# 05_SPI.net
KiCad netlist of a schematic drawn in Altium Designer
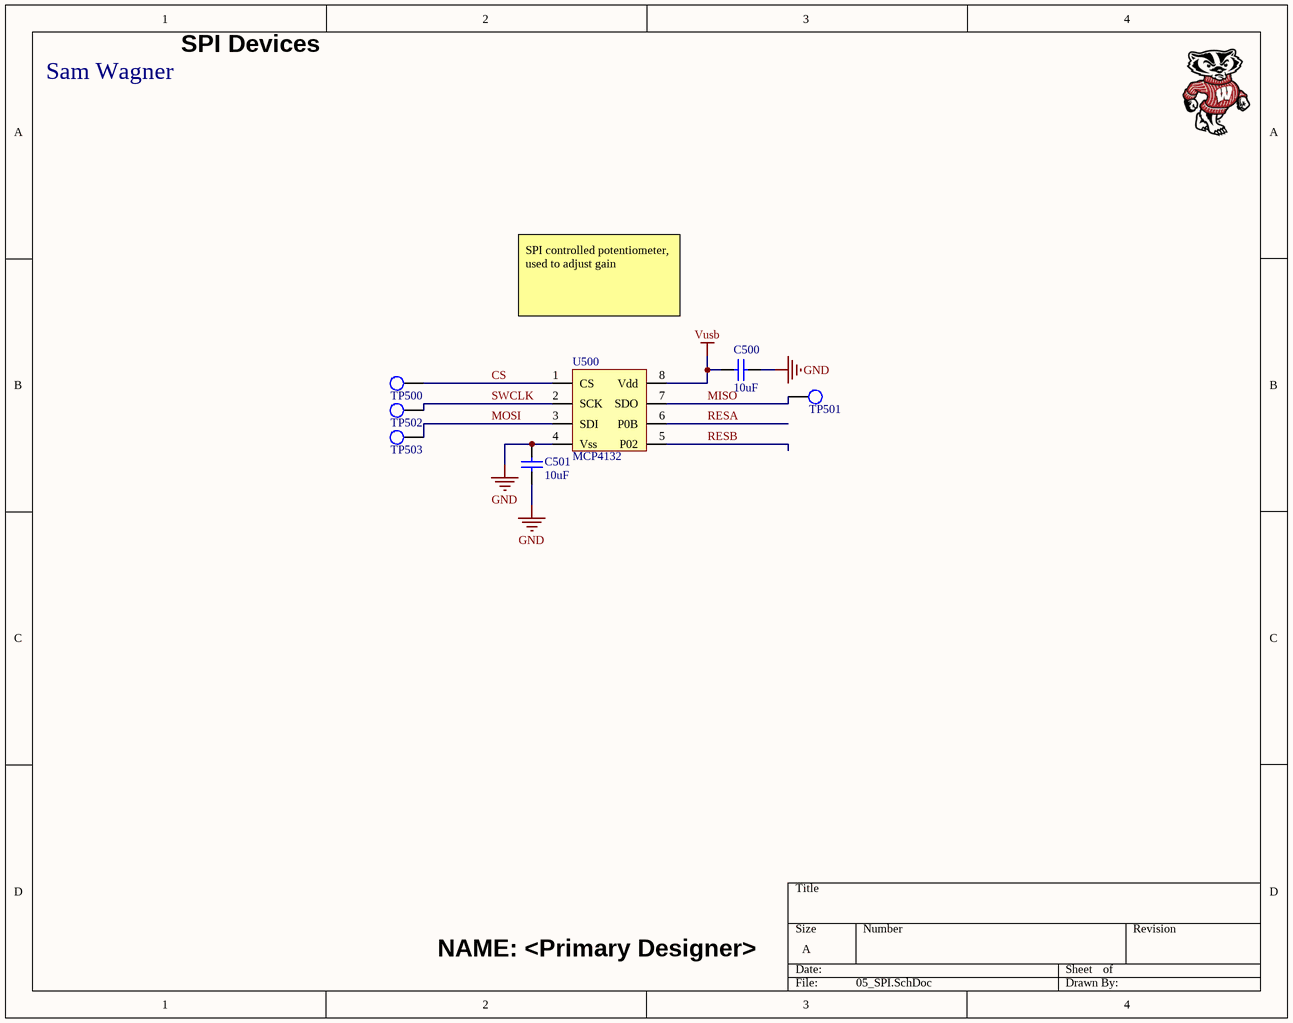
[diagram p0: 05_SPI.SchDoc]

(export (version "E")
  (design (tool "Eeschema 10.0.6"))
  (components
    (comp (ref "C500")
      (value "10uF")
      (footprint "CAP_0805")
      (description "CAP CER 10UF 16V X7R 0805")
      (fields
        (field (name "MANUFACTURER") "Samsung")
        (field (name "MANUFACTURER PART NUMBER") "CL21A106KPCLQNC")
        (field (name "CAPACITANCE") "10uF")
      )
      (libsource (lib "ece315-S20") (part "CAP_0805_U_010.00"))
    )
    (comp (ref "C501")
      (value "10uF")
      (footprint "CAP_0805")
      (description "CAP CER 10UF 16V X7R 0805")
      (fields
        (field (name "MANUFACTURER") "Samsung")
        (field (name "MANUFACTURER PART NUMBER") "CL21A106KPCLQNC")
        (field (name "CAPACITANCE") "10uF")
      )
      (libsource (lib "ece315-S20") (part "CAP_0805_U_010.00"))
    )
    (comp (ref "TP500")
      (value "TP_1206")
      (footprint "TP-SMC-1206")
      (description "Test Point SMD 1206")
      (fields
        (field (name "MANUFACTURER") "TE Connectivity (Tyco Electronics)")
        (field (name "MANUFACTURER PART NUMBER") "1625854-1")
      )
      (libsource (lib "ece315-S20") (part "TP_1206"))
    )
    (comp (ref "TP501")
      (value "TP_1206")
      (footprint "TP-SMC-1206")
      (description "Test Point SMD 1206")
      (fields
        (field (name "MANUFACTURER") "TE Connectivity (Tyco Electronics)")
        (field (name "MANUFACTURER PART NUMBER") "1625854-1")
      )
      (libsource (lib "ece315-S20") (part "TP_1206"))
    )
    (comp (ref "TP502")
      (value "TP_1206")
      (footprint "TP-SMC-1206")
      (description "Test Point SMD 1206")
      (fields
        (field (name "MANUFACTURER") "TE Connectivity (Tyco Electronics)")
        (field (name "MANUFACTURER PART NUMBER") "1625854-1")
      )
      (libsource (lib "ece315-S20") (part "TP_1206"))
    )
    (comp (ref "TP503")
      (value "TP_1206")
      (footprint "TP-SMC-1206")
      (description "Test Point SMD 1206")
      (fields
        (field (name "MANUFACTURER") "TE Connectivity (Tyco Electronics)")
        (field (name "MANUFACTURER PART NUMBER") "1625854-1")
      )
      (libsource (lib "ece315-S20") (part "TP_1206"))
    )
    (comp (ref "U500")
      (value "MCP4132")
      (footprint "DIP8")
      (description "Digital Potentiometer")
      (libsource (lib "Final_Project_Analog") (part "MCP4132"))
    )
  )
  (nets
    (net (code "1") (name "/CS") (class "Default")
      (node (ref "TP500") (pin "1") (pintype "passive"))
      (node (ref "U500") (pin "1") (pinfunction "CS_1") (pintype "passive"))
    )
    (net (code "2") (name "/MISO") (class "Default")
      (node (ref "TP501") (pin "1") (pintype "passive"))
      (node (ref "U500") (pin "7") (pinfunction "SDO_7") (pintype "passive"))
    )
    (net (code "3") (name "/MOSI") (class "Default")
      (node (ref "TP503") (pin "1") (pintype "passive"))
      (node (ref "U500") (pin "3") (pinfunction "SDI_3") (pintype "passive"))
    )
    (net (code "4") (name "/RESA") (class "Default")
      (node (ref "U500") (pin "6") (pinfunction "P0B_6") (pintype "passive"))
    )
    (net (code "5") (name "/RESB") (class "Default")
      (node (ref "U500") (pin "5") (pinfunction "P02_5") (pintype "passive"))
    )
    (net (code "6") (name "/SWCLK") (class "Default")
      (node (ref "TP502") (pin "1") (pintype "passive"))
      (node (ref "U500") (pin "2") (pinfunction "SCK_2") (pintype "passive"))
    )
    (net (code "7") (name "GND") (class "Default")
      (node (ref "C500") (pin "2") (pinfunction "2_2") (pintype "passive"))
      (node (ref "C501") (pin "1") (pinfunction "1_1") (pintype "passive"))
      (node (ref "C501") (pin "2") (pinfunction "2_2") (pintype "passive"))
      (node (ref "U500") (pin "4") (pinfunction "Vss_4") (pintype "passive"))
    )
    (net (code "8") (name "Vusb") (class "Default")
      (node (ref "C500") (pin "1") (pinfunction "1_1") (pintype "passive"))
      (node (ref "U500") (pin "8") (pinfunction "Vdd_8") (pintype "passive"))
    )
  )
)
